# tx.net
KiCad netlist of a schematic drawn in EAGLE
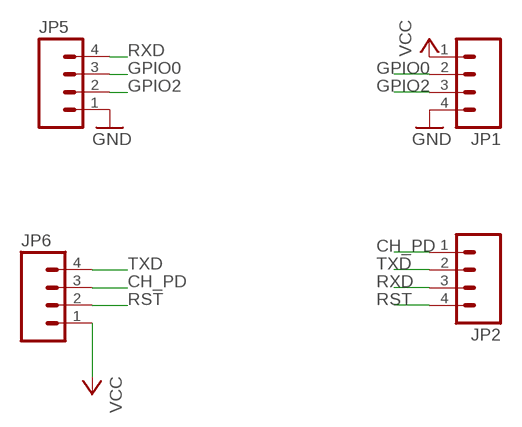
[diagram p0: schematic, sheet 1]

(export (version "E")
  (design (tool "Eeschema 10.0.6"))
  (components
    (comp (ref "JP1")
      (value "M04PTH")
      (footprint "eagle-import:1X04")
      (libsource (lib "eagle-import") (part "M04PTH"))
    )
    (comp (ref "JP2")
      (value "M04PTH")
      (footprint "eagle-import:1X04")
      (libsource (lib "eagle-import") (part "M04PTH"))
    )
    (comp (ref "JP5")
      (value "M041X04_NO_SILK")
      (footprint "eagle-import:1X04_NO_SILK")
      (libsource (lib "eagle-import") (part "M041X04_NO_SILK"))
    )
    (comp (ref "JP6")
      (value "M041X04_NO_SILK")
      (footprint "eagle-import:1X04_NO_SILK")
      (libsource (lib "eagle-import") (part "M041X04_NO_SILK"))
    )
  )
  (nets
    (net (code "1") (name "/CH_PD") (class "Default")
      (node (ref "JP2") (pin "1") (pinfunction "1_1") (pintype "passive"))
      (node (ref "JP6") (pin "3") (pinfunction "3_3") (pintype "passive"))
    )
    (net (code "2") (name "/GPIO0") (class "Default")
      (node (ref "JP1") (pin "2") (pinfunction "2_2") (pintype "passive"))
      (node (ref "JP5") (pin "3") (pinfunction "3_3") (pintype "passive"))
    )
    (net (code "3") (name "/GPIO2") (class "Default")
      (node (ref "JP1") (pin "3") (pinfunction "3_3") (pintype "passive"))
      (node (ref "JP5") (pin "2") (pinfunction "2_2") (pintype "passive"))
    )
    (net (code "4") (name "/RST") (class "Default")
      (node (ref "JP2") (pin "4") (pinfunction "4_4") (pintype "passive"))
      (node (ref "JP6") (pin "2") (pinfunction "2_2") (pintype "passive"))
    )
    (net (code "5") (name "/RXD") (class "Default")
      (node (ref "JP2") (pin "3") (pinfunction "3_3") (pintype "passive"))
      (node (ref "JP5") (pin "4") (pinfunction "4_4") (pintype "passive"))
    )
    (net (code "6") (name "/TXD") (class "Default")
      (node (ref "JP2") (pin "2") (pinfunction "2_2") (pintype "passive"))
      (node (ref "JP6") (pin "4") (pinfunction "4_4") (pintype "passive"))
    )
    (net (code "7") (name "GND") (class "Default")
      (node (ref "JP1") (pin "4") (pinfunction "4_4") (pintype "passive"))
      (node (ref "JP5") (pin "1") (pinfunction "1_1") (pintype "passive"))
    )
    (net (code "8") (name "VCC") (class "Default")
      (node (ref "JP1") (pin "1") (pinfunction "1_1") (pintype "passive"))
      (node (ref "JP6") (pin "1") (pinfunction "1_1") (pintype "passive"))
    )
  )
)
